# Schematic_v24.net
KiCad netlist of a schematic drawn in EAGLE
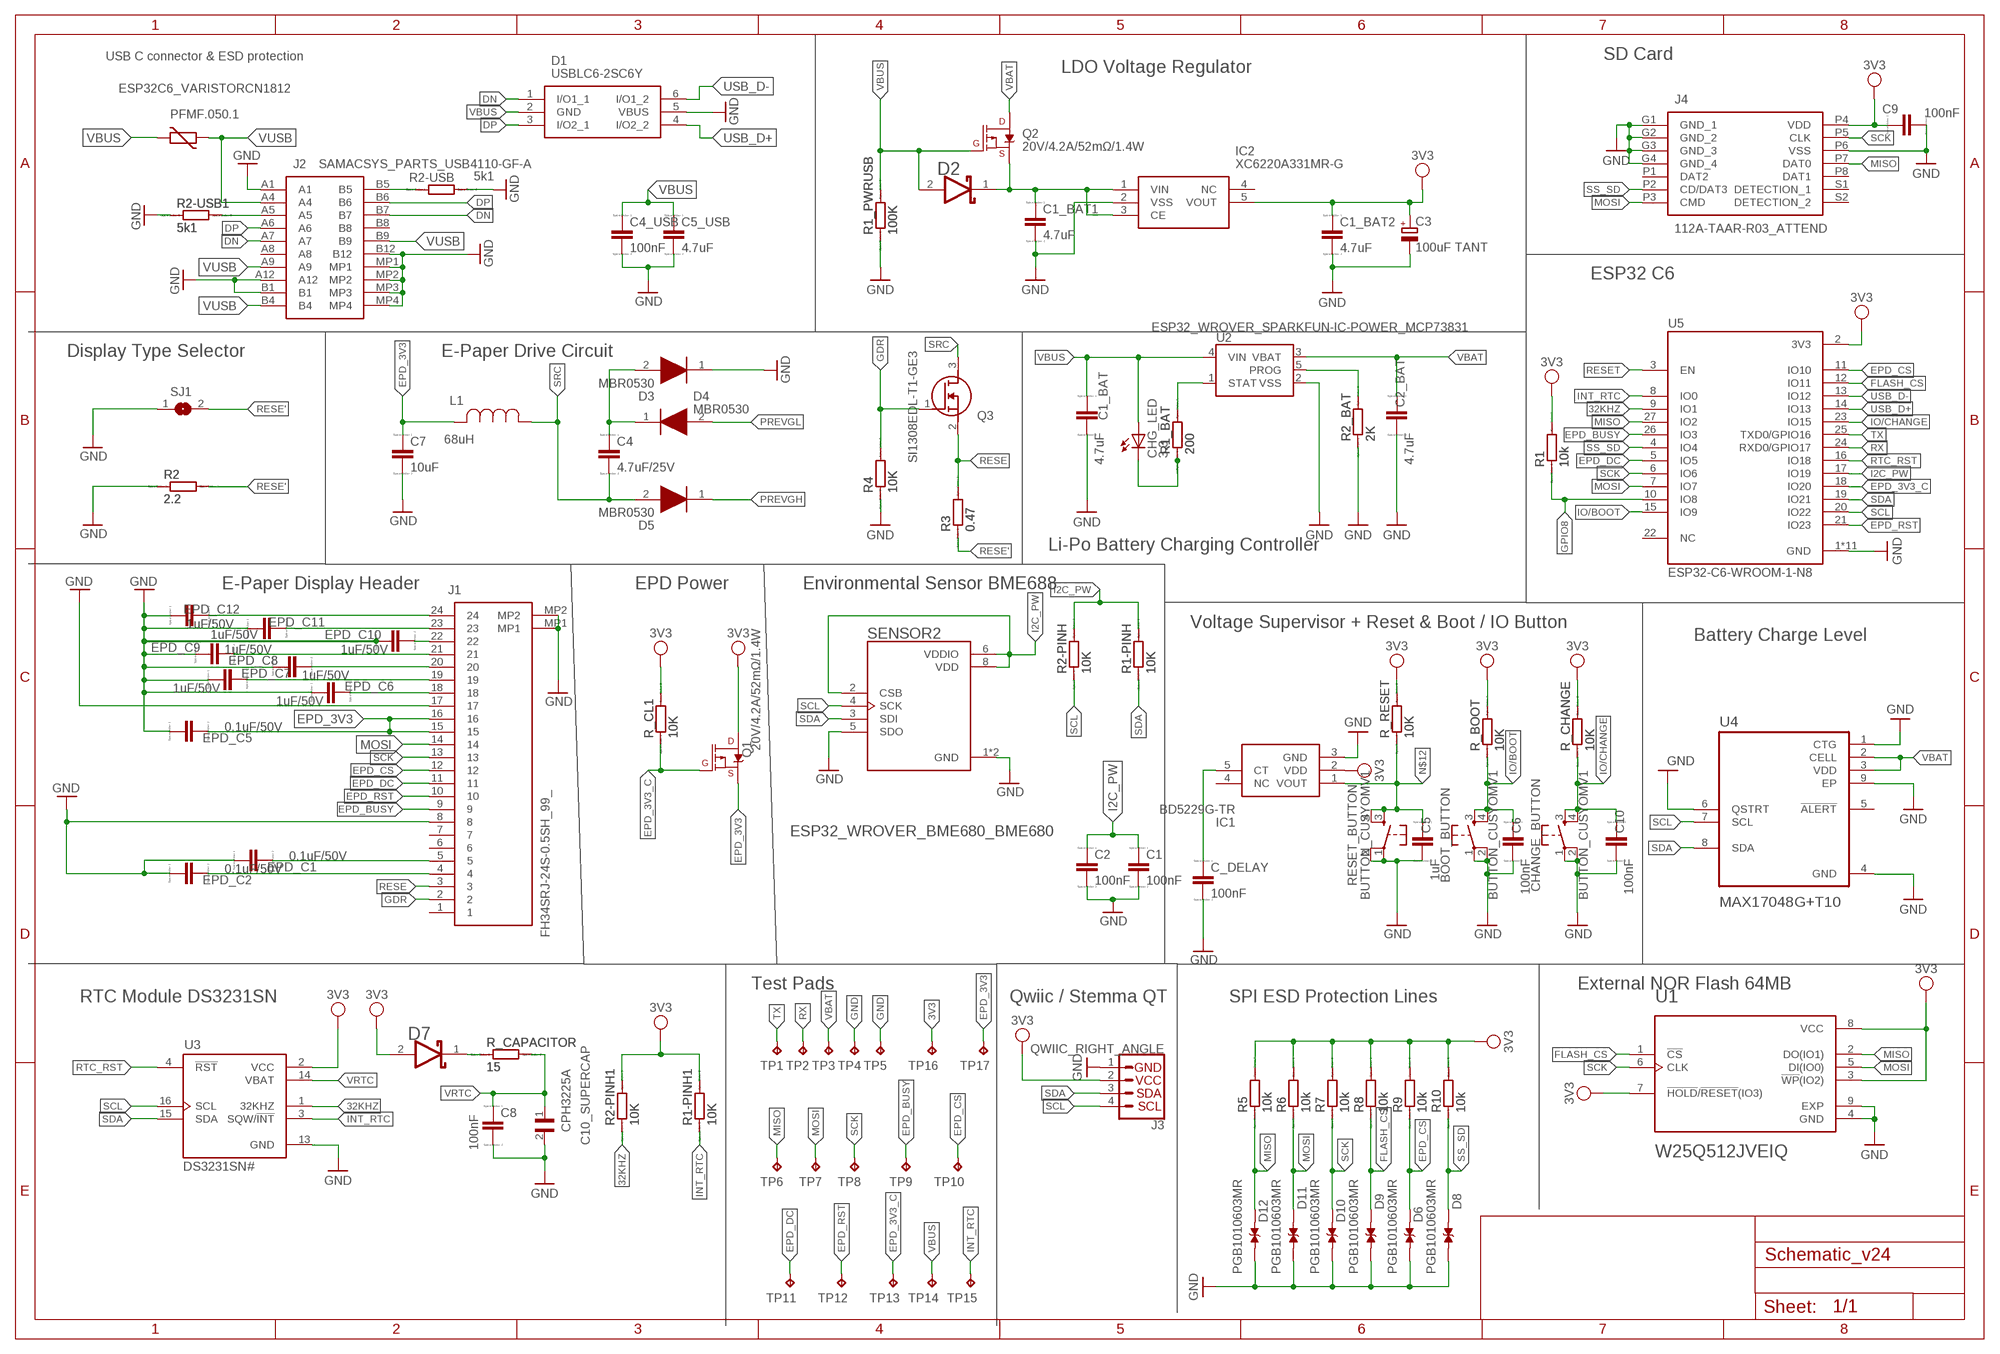
[diagram p0: schematic, sheet 1]

(export (version "E")
  (design (tool "Eeschema 10.0.6"))
  (components
    (comp (ref "BOOT_BUTTON")
      (value "BUTTON_CUSYOMV1")
      (footprint "eagle-import:MYBUTTON")
      (libsource (lib "eagle-import") (part "BUTTON_CUSYOMV1"))
    )
    (comp (ref "C1")
      (value "100nF")
      (footprint "eagle-import:ESP32_WROVER_EAGLE-LTSPICE_C0402")
      (libsource (lib "eagle-import") (part "ESP32_WROVER_EAGLE-LTSPICE_CC0402"))
    )
    (comp (ref "C1_BAT")
      (value "4.7uF")
      (footprint "eagle-import:ESP32_WROVER_EAGLE-LTSPICE_C0402")
      (libsource (lib "eagle-import") (part "ESP32_WROVER_EAGLE-LTSPICE_CC0402"))
    )
    (comp (ref "C1_BAT1")
      (value "4.7uF")
      (footprint "eagle-import:EAGLE-LTSPICE_C0402")
      (libsource (lib "eagle-import") (part "EAGLE-LTSPICE_CC0402"))
    )
    (comp (ref "C1_BAT2")
      (value "4.7uF")
      (footprint "eagle-import:EAGLE-LTSPICE_C0402")
      (libsource (lib "eagle-import") (part "EAGLE-LTSPICE_CC0402"))
    )
    (comp (ref "C2")
      (value "100nF")
      (footprint "eagle-import:ESP32_WROVER_EAGLE-LTSPICE_C0402")
      (libsource (lib "eagle-import") (part "ESP32_WROVER_EAGLE-LTSPICE_CC0402"))
    )
    (comp (ref "C2_BAT")
      (value "4.7uF")
      (footprint "eagle-import:ESP32_WROVER_EAGLE-LTSPICE_C0402")
      (libsource (lib "eagle-import") (part "ESP32_WROVER_EAGLE-LTSPICE_CC0402"))
    )
    (comp (ref "C3")
      (value "100uF TANT")
      (footprint "eagle-import:RCL_CT3528")
      (libsource (lib "eagle-import") (part "RCL_CPOL-EUCT3528"))
    )
    (comp (ref "C4")
      (value "4.7uF/25V")
      (footprint "eagle-import:ESP32_WROVER_EAGLE-LTSPICE_C0402")
      (libsource (lib "eagle-import") (part "ESP32_WROVER_EAGLE-LTSPICE_CC0402"))
    )
    (comp (ref "C4_USB")
      (value "100nF")
      (footprint "eagle-import:ESP32_WROVER_EAGLE-LTSPICE_C0402")
      (libsource (lib "eagle-import") (part "ESP32_WROVER_EAGLE-LTSPICE_CC0402"))
    )
    (comp (ref "C5")
      (value "1uF")
      (footprint "eagle-import:ESP32_WROVER_EAGLE-LTSPICE_C0402")
      (libsource (lib "eagle-import") (part "ESP32_WROVER_EAGLE-LTSPICE_CC0402"))
    )
    (comp (ref "C5_USB")
      (value "4.7uF")
      (footprint "eagle-import:ESP32_WROVER_EAGLE-LTSPICE_C0402")
      (libsource (lib "eagle-import") (part "ESP32_WROVER_EAGLE-LTSPICE_CC0402"))
    )
    (comp (ref "C6")
      (value "100nF")
      (footprint "eagle-import:ESP32_WROVER_EAGLE-LTSPICE_C0402")
      (libsource (lib "eagle-import") (part "ESP32_WROVER_EAGLE-LTSPICE_CC0402"))
    )
    (comp (ref "C7")
      (value "10uF")
      (footprint "eagle-import:ESP32_WROVER_EAGLE-LTSPICE_C0402")
      (libsource (lib "eagle-import") (part "ESP32_WROVER_EAGLE-LTSPICE_CC0402"))
    )
    (comp (ref "C8")
      (value "100nF")
      (footprint "eagle-import:ESP32_WROVER_EAGLE-LTSPICE_C0402")
      (libsource (lib "eagle-import") (part "ESP32_WROVER_EAGLE-LTSPICE_CC0402"))
    )
    (comp (ref "C9")
      (value "100nF")
      (footprint "eagle-import:ESP32_WROVER_EAGLE-LTSPICE_C0402")
      (libsource (lib "eagle-import") (part "ESP32_WROVER_EAGLE-LTSPICE_CC0402"))
    )
    (comp (ref "C10")
      (value "100nF")
      (footprint "eagle-import:ESP32_WROVER_EAGLE-LTSPICE_C0402")
      (libsource (lib "eagle-import") (part "ESP32_WROVER_EAGLE-LTSPICE_CC0402"))
    )
    (comp (ref "C10_SUPERCAP")
      (value "CPH3225A")
      (footprint "eagle-import:CAPCP3225X100N")
      (fields (field (name "MF") "Seiko Instruments"))
      (libsource (lib "eagle-import") (part "CPH3225A"))
    )
    (comp (ref "CHANGE_BUTTON")
      (value "BUTTON_CUSYOMV1")
      (footprint "eagle-import:MYBUTTON")
      (libsource (lib "eagle-import") (part "BUTTON_CUSYOMV1"))
    )
    (comp (ref "CHG_LED")
      (value "3.3")
      (footprint "eagle-import:ADAFRUIT_CHIP-LED0603")
      (libsource (lib "eagle-import") (part "ADAFRUIT_LEDCHIP-LED0603"))
    )
    (comp (ref "C_DELAY")
      (value "100nF")
      (footprint "eagle-import:ESP32_WROVER_EAGLE-LTSPICE_C0402")
      (libsource (lib "eagle-import") (part "ESP32_WROVER_EAGLE-LTSPICE_CC0402"))
    )
    (comp (ref "D1")
      (value "USBLC6-2SC6Y")
      (footprint "eagle-import:SOT95P280X145-6N")
      (fields (field (name "MF") "STMicroelectronics"))
      (libsource (lib "eagle-import") (part "USBLC6-2SC6Y"))
    )
    (comp (ref "D2")
      (value "ESP32_WROVER_AVX---SD0805S020S1R0_AVX_SD0805S020S1R0_0_0AVX_SD0805S020S1R0_0_0")
      (footprint "eagle-import:ESP32_WROVER_AVX---SD0805S020S1R0_AVX_SD0805S020S1R0_0")
      (fields
        (field (name "DIGIKEY_PART_NUMBER") "478-7800-1-ND")
        (field (name "MF") "AVX")
        (field (name "MOUSER_PART_NUMBER") "581-SD0805S020S1R0")
      )
      (libsource (lib "eagle-import") (part "ESP32_WROVER_AVX---SD0805S020S1R0_AVX_SD0805S020S1R0_0_0AVX_SD0805S020S1R0_0_0"))
    )
    (comp (ref "D3")
      (value "MBR0530")
      (footprint "eagle-import:SOD3716X135N")
      (fields (field (name "MF") "ON Semiconductor"))
      (libsource (lib "eagle-import") (part "MBR0530"))
    )
    (comp (ref "D4")
      (value "MBR0530")
      (footprint "eagle-import:SOD3716X135N")
      (fields (field (name "MF") "ON Semiconductor"))
      (libsource (lib "eagle-import") (part "MBR0530"))
    )
    (comp (ref "D5")
      (value "MBR0530")
      (footprint "eagle-import:SOD3716X135N")
      (fields (field (name "MF") "ON Semiconductor"))
      (libsource (lib "eagle-import") (part "MBR0530"))
    )
    (comp (ref "D6")
      (value "PGB1010603MR")
      (footprint "eagle-import:DIOC1608X36N")
      (fields (field (name "MF") "Littelfuse Inc."))
      (libsource (lib "eagle-import") (part "PGB1010603MR"))
    )
    (comp (ref "D7")
      (value "ESP32_WROVER_AVX---SD0805S020S1R0_AVX_SD0805S020S1R0_0_0AVX_SD0805S020S1R0_0_0")
      (footprint "eagle-import:ESP32_WROVER_AVX---SD0805S020S1R0_AVX_SD0805S020S1R0_0")
      (fields
        (field (name "DIGIKEY_PART_NUMBER") "478-7800-1-ND")
        (field (name "MF") "AVX")
        (field (name "MOUSER_PART_NUMBER") "581-SD0805S020S1R0")
      )
      (libsource (lib "eagle-import") (part "ESP32_WROVER_AVX---SD0805S020S1R0_AVX_SD0805S020S1R0_0_0AVX_SD0805S020S1R0_0_0"))
    )
    (comp (ref "D8")
      (value "PGB1010603MR")
      (footprint "eagle-import:DIOC1608X36N")
      (fields (field (name "MF") "Littelfuse Inc."))
      (libsource (lib "eagle-import") (part "PGB1010603MR"))
    )
    (comp (ref "D9")
      (value "PGB1010603MR")
      (footprint "eagle-import:DIOC1608X36N")
      (fields (field (name "MF") "Littelfuse Inc."))
      (libsource (lib "eagle-import") (part "PGB1010603MR"))
    )
    (comp (ref "D10")
      (value "PGB1010603MR")
      (footprint "eagle-import:DIOC1608X36N")
      (fields (field (name "MF") "Littelfuse Inc."))
      (libsource (lib "eagle-import") (part "PGB1010603MR"))
    )
    (comp (ref "D11")
      (value "PGB1010603MR")
      (footprint "eagle-import:DIOC1608X36N")
      (fields (field (name "MF") "Littelfuse Inc."))
      (libsource (lib "eagle-import") (part "PGB1010603MR"))
    )
    (comp (ref "D12")
      (value "PGB1010603MR")
      (footprint "eagle-import:DIOC1608X36N")
      (fields (field (name "MF") "Littelfuse Inc."))
      (libsource (lib "eagle-import") (part "PGB1010603MR"))
    )
    (comp (ref "EPD_C1")
      (value "0.1uF/50V")
      (footprint "eagle-import:ESP32_WROVER_EAGLE-LTSPICE_C0402")
      (libsource (lib "eagle-import") (part "ESP32_WROVER_EAGLE-LTSPICE_CC0402"))
    )
    (comp (ref "EPD_C2")
      (value "0.1uF/50V")
      (footprint "eagle-import:ESP32_WROVER_EAGLE-LTSPICE_C0402")
      (libsource (lib "eagle-import") (part "ESP32_WROVER_EAGLE-LTSPICE_CC0402"))
    )
    (comp (ref "EPD_C5")
      (value "0.1uF/50V")
      (footprint "eagle-import:ESP32_WROVER_EAGLE-LTSPICE_C0402")
      (libsource (lib "eagle-import") (part "ESP32_WROVER_EAGLE-LTSPICE_CC0402"))
    )
    (comp (ref "EPD_C6")
      (value "1uF/50V")
      (footprint "eagle-import:ESP32_WROVER_EAGLE-LTSPICE_C0402")
      (libsource (lib "eagle-import") (part "ESP32_WROVER_EAGLE-LTSPICE_CC0402"))
    )
    (comp (ref "EPD_C7")
      (value "1uF/50V")
      (footprint "eagle-import:ESP32_WROVER_EAGLE-LTSPICE_C0402")
      (libsource (lib "eagle-import") (part "ESP32_WROVER_EAGLE-LTSPICE_CC0402"))
    )
    (comp (ref "EPD_C8")
      (value "1uF/50V")
      (footprint "eagle-import:ESP32_WROVER_EAGLE-LTSPICE_C0402")
      (libsource (lib "eagle-import") (part "ESP32_WROVER_EAGLE-LTSPICE_CC0402"))
    )
    (comp (ref "EPD_C9")
      (value "1uF/50V")
      (footprint "eagle-import:ESP32_WROVER_EAGLE-LTSPICE_C0402")
      (libsource (lib "eagle-import") (part "ESP32_WROVER_EAGLE-LTSPICE_CC0402"))
    )
    (comp (ref "EPD_C10")
      (value "1uF/50V")
      (footprint "eagle-import:ESP32_WROVER_EAGLE-LTSPICE_C0402")
      (libsource (lib "eagle-import") (part "ESP32_WROVER_EAGLE-LTSPICE_CC0402"))
    )
    (comp (ref "EPD_C11")
      (value "1uF/50V")
      (footprint "eagle-import:ESP32_WROVER_EAGLE-LTSPICE_C0402")
      (libsource (lib "eagle-import") (part "ESP32_WROVER_EAGLE-LTSPICE_CC0402"))
    )
    (comp (ref "EPD_C12")
      (value "1uF/50V")
      (footprint "eagle-import:ESP32_WROVER_EAGLE-LTSPICE_C0402")
      (libsource (lib "eagle-import") (part "ESP32_WROVER_EAGLE-LTSPICE_CC0402"))
    )
    (comp (ref "IC1")
      (value "BD5229G-TR")
      (footprint "eagle-import:SOT95P280X125-5N")
      (fields (field (name "MOUSER_PART_NUMBER") "755-BD5229G-TR"))
      (libsource (lib "eagle-import") (part "BD5229G-TR"))
    )
    (comp (ref "IC2")
      (value "XC6220A331MR-G")
      (footprint "eagle-import:SOT95P280X120-5N")
      (fields (field (name "MOUSER_PART_NUMBER") "865-XC6220A331MR-G"))
      (libsource (lib "eagle-import") (part "XC6220A331MR-G"))
    )
    (comp (ref "J1")
      (value "FH34SRJ-24S-0.5SH_99_")
      (footprint "eagle-import:FH34SRJ24S05SH99")
      (fields
        (field (name "MANUFACTURER_PART_NUMBER") "FH34SRJ-24S-0.5SH(99)")
        (field (name "MOUSER_PART_NUMBER") "798-FH34SRJ24S05SH99")
      )
      (libsource (lib "eagle-import") (part "FH34SRJ-24S-0.5SH_99_"))
    )
    (comp (ref "J2")
      (value "SAMACSYS_PARTS_USB4110-GF-A")
      (footprint "eagle-import:SAMACSYS_PARTS_USB4110GFA")
      (fields
        (field (name "MANUFACTURER_PART_NUMBER") "USB4110-GF-A")
        (field (name "MOUSER_PART_NUMBER") "640-USB4110-GF-A")
      )
      (libsource (lib "eagle-import") (part "SAMACSYS_PARTS_USB4110-GF-A"))
    )
    (comp (ref "J3")
      (value "QWIIC_RIGHT_ANGLE")
      (footprint "eagle-import:JST04_1MM_RA")
      (libsource (lib "eagle-import") (part "QWIIC_CONNECTORJS-1MM"))
    )
    (comp (ref "J4")
      (value "112A-TAAR-R03_ATTEND")
      (footprint "eagle-import:112ATAARR03ATTEND")
      (fields (field (name "MANUFACTURER_PART_NUMBER") "112A-TAAR-R03 ATTEND"))
      (libsource (lib "eagle-import") (part "112A-TAAR-R03_ATTEND"))
    )
    (comp (ref "L1")
      (value "68uH")
      (footprint "eagle-import:IND_4828-WE-TPC_WRE")
      (fields
        (field (name "MANUFACTURER_PART_NUMBER") "744043680")
        (field (name "COPYRIGHT") "Copyright (C) 2024 Ultra Librarian. All rights reserved.")
      )
      (libsource (lib "eagle-import") (part "744043680IND_4828-WE-TPC_WRE"))
    )
    (comp (ref "PFMF.050.1")
      (value "ESP32C6_VARISTORCN1812")
      (footprint "eagle-import:ESP32C6_VARISTOR_CT_CN1812")
      (libsource (lib "eagle-import") (part "ESP32C6_VARISTORCN1812"))
    )
    (comp (ref "Q1")
      (value "20V/4.2A/52mΩ/1.4W")
      (footprint "eagle-import:ESP32_WROVER_SPARKFUN-DISCRETESEMI_SOT23-3")
      (libsource (lib "eagle-import") (part "ESP32_WROVER_SPARKFUN-DISCRETESEMI_MOSFET_PCH-DMG2305UX-7"))
    )
    (comp (ref "Q2")
      (value "20V/4.2A/52mΩ/1.4W")
      (footprint "eagle-import:ESP32_WROVER_SPARKFUN-DISCRETESEMI_SOT23-3")
      (libsource (lib "eagle-import") (part "ESP32_WROVER_SPARKFUN-DISCRETESEMI_MOSFET_PCH-DMG2305UX-7"))
    )
    (comp (ref "Q3")
      (value "SI1308EDL-T1-GE3")
      (footprint "eagle-import:SOT65P210X110-3N")
      (fields (field (name "MF") "Vishay Siliconix"))
      (libsource (lib "eagle-import") (part "SI1308EDL-T1-GE3"))
    )
    (comp (ref "R1")
      (value "10k")
      (footprint "eagle-import:ESP32_WROVER_EAGLE-LTSPICE_R0402")
      (libsource (lib "eagle-import") (part "ESP32_WROVER_EAGLE-LTSPICE_RR0402"))
    )
    (comp (ref "R1-PINH")
      (value "10K")
      (footprint "eagle-import:ESP32_WROVER_EAGLE-LTSPICE_R0402")
      (libsource (lib "eagle-import") (part "ESP32_WROVER_EAGLE-LTSPICE_RR0402"))
    )
    (comp (ref "R1-PINH1")
      (value "10K")
      (footprint "eagle-import:ESP32_WROVER_EAGLE-LTSPICE_R0402")
      (libsource (lib "eagle-import") (part "ESP32_WROVER_EAGLE-LTSPICE_RR0402"))
    )
    (comp (ref "R1_BAT")
      (value "200")
      (footprint "eagle-import:ESP32_WROVER_EAGLE-LTSPICE_R0402")
      (libsource (lib "eagle-import") (part "ESP32_WROVER_EAGLE-LTSPICE_RR0402"))
    )
    (comp (ref "R1_PWRUSB")
      (value "100K")
      (footprint "eagle-import:ESP32_WROVER_EAGLE-LTSPICE_R0402")
      (libsource (lib "eagle-import") (part "ESP32_WROVER_EAGLE-LTSPICE_RR0402"))
    )
    (comp (ref "R2")
      (value "2.2")
      (footprint "eagle-import:ESP32_WROVER_EAGLE-LTSPICE_R0402")
      (libsource (lib "eagle-import") (part "ESP32_WROVER_EAGLE-LTSPICE_RR0402"))
    )
    (comp (ref "R2-PINH")
      (value "10K")
      (footprint "eagle-import:ESP32_WROVER_EAGLE-LTSPICE_R0402")
      (libsource (lib "eagle-import") (part "ESP32_WROVER_EAGLE-LTSPICE_RR0402"))
    )
    (comp (ref "R2-PINH1")
      (value "10K")
      (footprint "eagle-import:ESP32_WROVER_EAGLE-LTSPICE_R0402")
      (libsource (lib "eagle-import") (part "ESP32_WROVER_EAGLE-LTSPICE_RR0402"))
    )
    (comp (ref "R2-USB")
      (value "5k1")
      (footprint "eagle-import:ESP32_WROVER_EAGLE-LTSPICE_R0402")
      (libsource (lib "eagle-import") (part "ESP32_WROVER_EAGLE-LTSPICE_RR0402"))
    )
    (comp (ref "R2-USB1")
      (value "5k1")
      (footprint "eagle-import:ESP32_WROVER_EAGLE-LTSPICE_R0402")
      (libsource (lib "eagle-import") (part "ESP32_WROVER_EAGLE-LTSPICE_RR0402"))
    )
    (comp (ref "R2_BAT")
      (value "2K")
      (footprint "eagle-import:ESP32_WROVER_EAGLE-LTSPICE_R0402")
      (libsource (lib "eagle-import") (part "ESP32_WROVER_EAGLE-LTSPICE_RR0402"))
    )
    (comp (ref "R3")
      (value "0.47")
      (footprint "eagle-import:ESP32_WROVER_EAGLE-LTSPICE_R0402")
      (libsource (lib "eagle-import") (part "ESP32_WROVER_EAGLE-LTSPICE_RR0402"))
    )
    (comp (ref "R4")
      (value "10K")
      (footprint "eagle-import:ESP32_WROVER_EAGLE-LTSPICE_R0402")
      (libsource (lib "eagle-import") (part "ESP32_WROVER_EAGLE-LTSPICE_RR0402"))
    )
    (comp (ref "R5")
      (value "10k")
      (footprint "eagle-import:ESP32_WROVER_EAGLE-LTSPICE_R0402")
      (libsource (lib "eagle-import") (part "ESP32_WROVER_EAGLE-LTSPICE_RR0402"))
    )
    (comp (ref "R6")
      (value "10k")
      (footprint "eagle-import:ESP32_WROVER_EAGLE-LTSPICE_R0402")
      (libsource (lib "eagle-import") (part "ESP32_WROVER_EAGLE-LTSPICE_RR0402"))
    )
    (comp (ref "R7")
      (value "10k")
      (footprint "eagle-import:ESP32_WROVER_EAGLE-LTSPICE_R0402")
      (libsource (lib "eagle-import") (part "ESP32_WROVER_EAGLE-LTSPICE_RR0402"))
    )
    (comp (ref "R8")
      (value "10k")
      (footprint "eagle-import:ESP32_WROVER_EAGLE-LTSPICE_R0402")
      (libsource (lib "eagle-import") (part "ESP32_WROVER_EAGLE-LTSPICE_RR0402"))
    )
    (comp (ref "R9")
      (value "10k")
      (footprint "eagle-import:ESP32_WROVER_EAGLE-LTSPICE_R0402")
      (libsource (lib "eagle-import") (part "ESP32_WROVER_EAGLE-LTSPICE_RR0402"))
    )
    (comp (ref "R10")
      (value "10k")
      (footprint "eagle-import:ESP32_WROVER_EAGLE-LTSPICE_R0402")
      (libsource (lib "eagle-import") (part "ESP32_WROVER_EAGLE-LTSPICE_RR0402"))
    )
    (comp (ref "RESET_BUTTON")
      (value "BUTTON_CUSYOMV1")
      (footprint "eagle-import:MYBUTTON")
      (libsource (lib "eagle-import") (part "BUTTON_CUSYOMV1"))
    )
    (comp (ref "R_BOOT")
      (value "10K")
      (footprint "eagle-import:ESP32_WROVER_EAGLE-LTSPICE_R0402")
      (libsource (lib "eagle-import") (part "ESP32_WROVER_EAGLE-LTSPICE_RR0402"))
    )
    (comp (ref "R_CAPACITOR")
      (value "15")
      (footprint "eagle-import:ESP32_WROVER_EAGLE-LTSPICE_R0402")
      (libsource (lib "eagle-import") (part "ESP32_WROVER_EAGLE-LTSPICE_RR0402"))
    )
    (comp (ref "R_CHANGE")
      (value "10K")
      (footprint "eagle-import:ESP32_WROVER_EAGLE-LTSPICE_R0402")
      (libsource (lib "eagle-import") (part "ESP32_WROVER_EAGLE-LTSPICE_RR0402"))
    )
    (comp (ref "R_CL1")
      (value "10K")
      (footprint "eagle-import:ESP32_WROVER_EAGLE-LTSPICE_R0402")
      (libsource (lib "eagle-import") (part "ESP32_WROVER_EAGLE-LTSPICE_RR0402"))
    )
    (comp (ref "R_RESET")
      (value "10K")
      (footprint "eagle-import:ESP32_WROVER_EAGLE-LTSPICE_R0402")
      (libsource (lib "eagle-import") (part "ESP32_WROVER_EAGLE-LTSPICE_RR0402"))
    )
    (comp (ref "SENSOR2")
      (value "ESP32_WROVER_BME680_BME680")
      (footprint "eagle-import:ESP32_WROVER_BME680_PSON80P300X300X100-8N")
      (fields (field (name "MF") "Bosch Sensortec") (field (name "MP") "BME680"))
      (libsource (lib "eagle-import") (part "ESP32_WROVER_BME680_BME680"))
    )
    (comp (ref "SJ1") (value "SJ") (footprint "eagle-import:SJ") (libsource (lib "eagle-import") (part "SJ")))
    (comp (ref "TP1")
      (value "TPTP20R")
      (footprint "eagle-import:TP20R")
      (libsource (lib "eagle-import") (part "TPTP20R"))
    )
    (comp (ref "TP2")
      (value "TPTP20R")
      (footprint "eagle-import:TP20R")
      (libsource (lib "eagle-import") (part "TPTP20R"))
    )
    (comp (ref "TP3")
      (value "TPTP20R")
      (footprint "eagle-import:TP20R")
      (libsource (lib "eagle-import") (part "TPTP20R"))
    )
    (comp (ref "TP4")
      (value "TPTP20R")
      (footprint "eagle-import:TP20R")
      (libsource (lib "eagle-import") (part "TPTP20R"))
    )
    (comp (ref "TP5")
      (value "TPTP20R")
      (footprint "eagle-import:TP20R")
      (libsource (lib "eagle-import") (part "TPTP20R"))
    )
    (comp (ref "TP6")
      (value "TPTP20R")
      (footprint "eagle-import:TP20R")
      (libsource (lib "eagle-import") (part "TPTP20R"))
    )
    (comp (ref "TP7")
      (value "TPTP20R")
      (footprint "eagle-import:TP20R")
      (libsource (lib "eagle-import") (part "TPTP20R"))
    )
    (comp (ref "TP8")
      (value "TPTP20R")
      (footprint "eagle-import:TP20R")
      (libsource (lib "eagle-import") (part "TPTP20R"))
    )
    (comp (ref "TP9")
      (value "TPTP20R")
      (footprint "eagle-import:TP20R")
      (libsource (lib "eagle-import") (part "TPTP20R"))
    )
    (comp (ref "TP10")
      (value "TPTP20R")
      (footprint "eagle-import:TP20R")
      (libsource (lib "eagle-import") (part "TPTP20R"))
    )
    (comp (ref "TP11")
      (value "TPTP20R")
      (footprint "eagle-import:TP20R")
      (libsource (lib "eagle-import") (part "TPTP20R"))
    )
    (comp (ref "TP12")
      (value "TPTP20R")
      (footprint "eagle-import:TP20R")
      (libsource (lib "eagle-import") (part "TPTP20R"))
    )
    (comp (ref "TP13")
      (value "TPTP20R")
      (footprint "eagle-import:TP20R")
      (libsource (lib "eagle-import") (part "TPTP20R"))
    )
    (comp (ref "TP14")
      (value "TPTP20R")
      (footprint "eagle-import:TP20R")
      (libsource (lib "eagle-import") (part "TPTP20R"))
    )
    (comp (ref "TP15")
      (value "TPTP20R")
      (footprint "eagle-import:TP20R")
      (libsource (lib "eagle-import") (part "TPTP20R"))
    )
    (comp (ref "TP16")
      (value "TPTP20R")
      (footprint "eagle-import:TP20R")
      (libsource (lib "eagle-import") (part "TPTP20R"))
    )
    (comp (ref "TP17")
      (value "TPTP20R")
      (footprint "eagle-import:TP20R")
      (libsource (lib "eagle-import") (part "TPTP20R"))
    )
    (comp (ref "U1")
      (value "W25Q512JVEIQ")
      (footprint "eagle-import:SON127P600X800X80-9N")
      (fields (field (name "MF") "Winbond Electronics"))
      (libsource (lib "eagle-import") (part "W25Q512JVEIQ"))
    )
    (comp (ref "U2")
      (value "ESP32_WROVER_SPARKFUN-IC-POWER_MCP73831")
      (footprint "eagle-import:ESP32_WROVER_SPARKFUN-IC-POWER_SOT23-5")
      (libsource (lib "eagle-import") (part "ESP32_WROVER_SPARKFUN-IC-POWER_MCP73831"))
    )
    (comp (ref "U3")
      (value "DS3231SN#")
      (footprint "eagle-import:SOIC127P1032X265-16N")
      (fields (field (name "MF") "Analog Devices"))
      (libsource (lib "eagle-import") (part "DS3231SN#"))
    )
    (comp (ref "U4")
      (value "MAX17048G+T10")
      (footprint "eagle-import:SON50P200X200X80-9N")
      (fields (field (name "MF") "Analog Devices"))
      (libsource (lib "eagle-import") (part "MAX17048G+T10"))
    )
    (comp (ref "U5")
      (value "ESP32-C6-WROOM-1-N8")
      (footprint "eagle-import:XCVR_ESP32-C6-WROOM-1-N8")
      (fields (field (name "MF") "Espressif Systems"))
      (libsource (lib "eagle-import") (part "ESP32-C6-WROOM-1-N8"))
    )
  )
  (nets
    (net (code "1") (name "3V3") (class "Default")
      (node (ref "C1_BAT2") (pin "1") (pinfunction "1_1") (pintype "passive"))
      (node (ref "C3") (pin "+") (pinfunction "+_+") (pintype "passive"))
      (node (ref "C9") (pin "1") (pinfunction "1_1") (pintype "passive"))
      (node (ref "D7") (pin "2") (pinfunction "ANODE_2") (pintype "bidirectional"))
      (node (ref "IC1") (pin "2") (pinfunction "VDD_2") (pintype "bidirectional"))
      (node (ref "IC2") (pin "5") (pinfunction "VOUT_5") (pintype "bidirectional"))
      (node (ref "J3") (pin "2") (pinfunction "2_2") (pintype "power_in"))
      (node (ref "J4") (pin "P4") (pinfunction "VDD_P4") (pintype "bidirectional"))
      (node (ref "Q1") (pin "3") (pinfunction "D_3") (pintype "bidirectional"))
      (node (ref "R1") (pin "2") (pinfunction "2_2") (pintype "passive"))
      (node (ref "R1-PINH1") (pin "2") (pinfunction "2_2") (pintype "passive"))
      (node (ref "R10") (pin "2") (pinfunction "2_2") (pintype "passive"))
      (node (ref "R2-PINH1") (pin "2") (pinfunction "2_2") (pintype "passive"))
      (node (ref "R5") (pin "2") (pinfunction "2_2") (pintype "passive"))
      (node (ref "R6") (pin "2") (pinfunction "2_2") (pintype "passive"))
      (node (ref "R7") (pin "2") (pinfunction "2_2") (pintype "passive"))
      (node (ref "R8") (pin "2") (pinfunction "2_2") (pintype "passive"))
      (node (ref "R9") (pin "2") (pinfunction "2_2") (pintype "passive"))
      (node (ref "R_BOOT") (pin "2") (pinfunction "2_2") (pintype "passive"))
      (node (ref "R_CHANGE") (pin "2") (pinfunction "2_2") (pintype "passive"))
      (node (ref "R_CL1") (pin "2") (pinfunction "2_2") (pintype "passive"))
      (node (ref "R_RESET") (pin "2") (pinfunction "2_2") (pintype "passive"))
      (node (ref "TP16") (pin "TP") (pinfunction "TP_TP") (pintype "input"))
      (node (ref "U1") (pin "3") (pinfunction "~{WP}(IO2)_3") (pintype "bidirectional"))
      (node (ref "U1") (pin "7") (pinfunction "~{HOLD}/~{RESET}(IO3)_7") (pintype "bidirectional"))
      (node (ref "U1") (pin "8") (pinfunction "VCC_8") (pintype "power_in"))
      (node (ref "U3") (pin "2") (pinfunction "VCC_2") (pintype "power_in"))
      (node (ref "U5") (pin "2") (pinfunction "3V3_2") (pintype "power_in"))
    )
    (net (code "2") (name "32KHZ") (class "Default")
      (node (ref "R2-PINH1") (pin "1") (pinfunction "1_1") (pintype "passive"))
      (node (ref "U3") (pin "1") (pinfunction "32KHZ_1") (pintype "output"))
      (node (ref "U5") (pin "9") (pinfunction "IO1_9") (pintype "bidirectional"))
    )
    (net (code "3") (name "DN") (class "Default")
      (node (ref "D1") (pin "1") (pinfunction "I/O1_1_1") (pintype "bidirectional"))
      (node (ref "J2") (pin "A7") (pinfunction "A7_A7") (pintype "bidirectional"))
      (node (ref "J2") (pin "B7") (pinfunction "B7_B7") (pintype "bidirectional"))
    )
    (net (code "4") (name "DP") (class "Default")
      (node (ref "D1") (pin "3") (pinfunction "I/O2_1_3") (pintype "bidirectional"))
      (node (ref "J2") (pin "A6") (pinfunction "A6_A6") (pintype "bidirectional"))
      (node (ref "J2") (pin "B6") (pinfunction "B6_B6") (pintype "bidirectional"))
    )
    (net (code "5") (name "EPD_3V3") (class "Default")
      (node (ref "C7") (pin "1") (pinfunction "1_1") (pintype "passive"))
      (node (ref "EPD_C5") (pin "2") (pinfunction "2_2") (pintype "passive"))
      (node (ref "J1") (pin "15") (pinfunction "15_15") (pintype "bidirectional"))
      (node (ref "J1") (pin "16") (pinfunction "16_16") (pintype "bidirectional"))
      (node (ref "L1") (pin "2") (pinfunction "2_2") (pintype "passive"))
      (node (ref "Q1") (pin "2") (pinfunction "S_2") (pintype "bidirectional"))
      (node (ref "TP17") (pin "TP") (pinfunction "TP_TP") (pintype "input"))
    )
    (net (code "6") (name "EPD_3V3_C") (class "Default")
      (node (ref "Q1") (pin "1") (pinfunction "G_1") (pintype "bidirectional"))
      (node (ref "R_CL1") (pin "1") (pinfunction "1_1") (pintype "passive"))
      (node (ref "TP13") (pin "TP") (pinfunction "TP_TP") (pintype "input"))
      (node (ref "U5") (pin "18") (pinfunction "IO20_18") (pintype "bidirectional"))
    )
    (net (code "7") (name "EPD_BUSY") (class "Default")
      (node (ref "J1") (pin "9") (pinfunction "9_9") (pintype "bidirectional"))
      (node (ref "TP9") (pin "TP") (pinfunction "TP_TP") (pintype "input"))
      (node (ref "U5") (pin "26") (pinfunction "IO3_26") (pintype "bidirectional"))
    )
    (net (code "8") (name "EPD_CS") (class "Default")
      (node (ref "D6") (pin "2") (pinfunction "2_2") (pintype "passive"))
      (node (ref "J1") (pin "12") (pinfunction "12_12") (pintype "bidirectional"))
      (node (ref "R9") (pin "1") (pinfunction "1_1") (pintype "passive"))
      (node (ref "TP10") (pin "TP") (pinfunction "TP_TP") (pintype "input"))
      (node (ref "U5") (pin "11") (pinfunction "IO10_11") (pintype "bidirectional"))
    )
    (net (code "9") (name "EPD_DC") (class "Default")
      (node (ref "J1") (pin "11") (pinfunction "11_11") (pintype "bidirectional"))
      (node (ref "TP11") (pin "TP") (pinfunction "TP_TP") (pintype "input"))
      (node (ref "U5") (pin "5") (pinfunction "IO5_5") (pintype "bidirectional"))
    )
    (net (code "10") (name "EPD_RST") (class "Default")
      (node (ref "J1") (pin "10") (pinfunction "10_10") (pintype "bidirectional"))
      (node (ref "TP12") (pin "TP") (pinfunction "TP_TP") (pintype "input"))
      (node (ref "U5") (pin "21") (pinfunction "IO23_21") (pintype "bidirectional"))
    )
    (net (code "11") (name "FLASH_CS") (class "Default")
      (node (ref "D9") (pin "2") (pinfunction "2_2") (pintype "passive"))
      (node (ref "R8") (pin "1") (pinfunction "1_1") (pintype "passive"))
      (node (ref "U1") (pin "1") (pinfunction "~{CS}_1") (pintype "input"))
      (node (ref "U5") (pin "12") (pinfunction "IO11_12") (pintype "bidirectional"))
    )
    (net (code "12") (name "GDR") (class "Default")
      (node (ref "J1") (pin "2") (pinfunction "2_2") (pintype "bidirectional"))
      (node (ref "Q3") (pin "1") (pinfunction "G_1") (pintype "bidirectional"))
      (node (ref "R4") (pin "2") (pinfunction "2_2") (pintype "passive"))
    )
    (net (code "13") (name "GND") (class "Default")
      (node (ref "BOOT_BUTTON") (pin "1") (pinfunction "1_1") (pintype "passive"))
      (node (ref "BOOT_BUTTON") (pin "2") (pinfunction "2_2") (pintype "passive"))
      (node (ref "C1") (pin "2") (pinfunction "2_2") (pintype "passive"))
      (node (ref "C10") (pin "2") (pinfunction "2_2") (pintype "passive"))
      (node (ref "C10_SUPERCAP") (pin "2") (pinfunction "2_2") (pintype "passive"))
      (node (ref "C1_BAT") (pin "2") (pinfunction "2_2") (pintype "passive"))
      (node (ref "C1_BAT1") (pin "2") (pinfunction "2_2") (pintype "passive"))
      (node (ref "C1_BAT2") (pin "2") (pinfunction "2_2") (pintype "passive"))
      (node (ref "C2") (pin "2") (pinfunction "2_2") (pintype "passive"))
      (node (ref "C2_BAT") (pin "2") (pinfunction "2_2") (pintype "passive"))
      (node (ref "C3") (pin "-") (pinfunction "-_-") (pintype "passive"))
      (node (ref "C4_USB") (pin "2") (pinfunction "2_2") (pintype "passive"))
      (node (ref "C5") (pin "2") (pinfunction "2_2") (pintype "passive"))
      (node (ref "C5_USB") (pin "2") (pinfunction "2_2") (pintype "passive"))
      (node (ref "C6") (pin "2") (pinfunction "2_2") (pintype "passive"))
      (node (ref "C7") (pin "2") (pinfunction "2_2") (pintype "passive"))
      (node (ref "C8") (pin "2") (pinfunction "2_2") (pintype "passive"))
      (node (ref "C9") (pin "2") (pinfunction "2_2") (pintype "passive"))
      (node (ref "CHANGE_BUTTON") (pin "1") (pinfunction "1_1") (pintype "passive"))
      (node (ref "CHANGE_BUTTON") (pin "2") (pinfunction "2_2") (pintype "passive"))
      (node (ref "C_DELAY") (pin "2") (pinfunction "2_2") (pintype "passive"))
      (node (ref "D1") (pin "5") (pinfunction "VBUS_5") (pintype "bidirectional"))
      (node (ref "D10") (pin "1") (pinfunction "1_1") (pintype "passive"))
      (node (ref "D11") (pin "1") (pinfunction "1_1") (pintype "passive"))
      (node (ref "D12") (pin "1") (pinfunction "1_1") (pintype "passive"))
      (node (ref "D3") (pin "1") (pinfunction "K_1") (pintype "bidirectional"))
      (node (ref "D6") (pin "1") (pinfunction "1_1") (pintype "passive"))
      (node (ref "D8") (pin "1") (pinfunction "1_1") (pintype "passive"))
      (node (ref "D9") (pin "1") (pinfunction "1_1") (pintype "passive"))
      (node (ref "EPD_C1") (pin "1") (pinfunction "1_1") (pintype "passive"))
      (node (ref "EPD_C10") (pin "1") (pinfunction "1_1") (pintype "passive"))
      (node (ref "EPD_C11") (pin "1") (pinfunction "1_1") (pintype "passive"))
      (node (ref "EPD_C12") (pin "1") (pinfunction "1_1") (pintype "passive"))
      (node (ref "EPD_C2") (pin "1") (pinfunction "1_1") (pintype "passive"))
      (node (ref "EPD_C5") (pin "1") (pinfunction "1_1") (pintype "passive"))
      (node (ref "EPD_C6") (pin "1") (pinfunction "1_1") (pintype "passive"))
      (node (ref "EPD_C7") (pin "1") (pinfunction "1_1") (pintype "passive"))
      (node (ref "EPD_C8") (pin "1") (pinfunction "1_1") (pintype "passive"))
      (node (ref "EPD_C9") (pin "1") (pinfunction "1_1") (pintype "passive"))
      (node (ref "IC1") (pin "3") (pinfunction "GND_3") (pintype "bidirectional"))
      (node (ref "IC2") (pin "2") (pinfunction "VSS_2") (pintype "bidirectional"))
      (node (ref "J1") (pin "17") (pinfunction "17_17") (pintype "bidirectional"))
      (node (ref "J1") (pin "8") (pinfunction "8_8") (pintype "bidirectional"))
      (node (ref "J1") (pin "MP1") (pinfunction "MP1_MP1") (pintype "bidirectional"))
      (node (ref "J1") (pin "MP2") (pinfunction "MP2_MP2") (pintype "bidirectional"))
      (node (ref "J2") (pin "A1") (pinfunction "A1_A1") (pintype "bidirectional"))
      (node (ref "J2") (pin "A12") (pinfunction "A12_A12") (pintype "bidirectional"))
      (node (ref "J2") (pin "B1") (pinfunction "B1_B1") (pintype "bidirectional"))
      (node (ref "J2") (pin "B12") (pinfunction "B12_B12") (pintype "bidirectional"))
      (node (ref "J2") (pin "MP1") (pinfunction "MP1_MP1") (pintype "bidirectional"))
      (node (ref "J2") (pin "MP2") (pinfunction "MP2_MP2") (pintype "bidirectional"))
      (node (ref "J2") (pin "MP3") (pinfunction "MP3_MP3") (pintype "bidirectional"))
      (node (ref "J2") (pin "MP4") (pinfunction "MP4_MP4") (pintype "bidirectional"))
      (node (ref "J3") (pin "1") (pinfunction "1_1") (pintype "power_in"))
      (node (ref "J4") (pin "G1") (pinfunction "GND_1_G1") (pintype "bidirectional"))
      (node (ref "J4") (pin "G2") (pinfunction "GND_2_G2") (pintype "bidirectional"))
      (node (ref "J4") (pin "G3") (pinfunction "GND_3_G3") (pintype "bidirectional"))
      (node (ref "J4") (pin "G4") (pinfunction "GND_4_G4") (pintype "bidirectional"))
      (node (ref "J4") (pin "P6") (pinfunction "VSS_P6") (pintype "bidirectional"))
      (node (ref "R1_PWRUSB") (pin "1") (pinfunction "1_1") (pintype "passive"))
      (node (ref "R2") (pin "1") (pinfunction "1_1") (pintype "passive"))
      (node (ref "R2-USB") (pin "2") (pinfunction "2_2") (pintype "passive"))
      (node (ref "R2-USB1") (pin "1") (pinfunction "1_1") (pintype "passive"))
      (node (ref "R2_BAT") (pin "1") (pinfunction "1_1") (pintype "passive"))
      (node (ref "R4") (pin "1") (pinfunction "1_1") (pintype "passive"))
      (node (ref "RESET_BUTTON") (pin "1") (pinfunction "1_1") (pintype "passive"))
      (node (ref "RESET_BUTTON") (pin "2") (pinfunction "2_2") (pintype "passive"))
      (node (ref "SENSOR2") (pin "1") (pinfunction "GND_1") (pintype "power_in"))
      (node (ref "SENSOR2") (pin "5") (pinfunction "SDO_5") (pintype "bidirectional"))
      (node (ref "SENSOR2") (pin "7") (pinfunction "GND_7") (pintype "power_in"))
      (node (ref "SJ1") (pin "1") (pinfunction "1_1") (pintype "passive"))
      (node (ref "TP4") (pin "TP") (pinfunction "TP_TP") (pintype "input"))
      (node (ref "TP5") (pin "TP") (pinfunction "TP_TP") (pintype "input"))
      (node (ref "U1") (pin "4") (pinfunction "GND_4") (pintype "power_in"))
      (node (ref "U1") (pin "9") (pinfunction "EXP_9") (pintype "passive"))
      (node (ref "U2") (pin "2") (pinfunction "VSS_2") (pintype "power_in"))
      (node (ref "U3") (pin "13") (pinfunction "GND_13") (pintype "power_in"))
      (node (ref "U4") (pin "1") (pinfunction "CTG_1") (pintype "power_in"))
      (node (ref "U4") (pin "4") (pinfunction "GND_4") (pintype "power_in"))
      (node (ref "U4") (pin "6") (pinfunction "QSTRT_6") (pintype "input"))
      (node (ref "U4") (pin "9") (pinfunction "EP_9") (pintype "power_in"))
      (node (ref "U5") (pin "1") (pinfunction "GND_1") (pintype "power_in"))
      (node (ref "U5") (pin "28") (pinfunction "GND_28") (pintype "power_in"))
      (node (ref "U5") (pin "29_1") (pinfunction "GND_29_1") (pintype "power_in"))
      (node (ref "U5") (pin "29_2") (pinfunction "GND_29_2") (pintype "power_in"))
      (node (ref "U5") (pin "29_3") (pinfunction "GND_29_3") (pintype "power_in"))
      (node (ref "U5") (pin "29_4") (pinfunction "GND_29_4") (pintype "power_in"))
      (node (ref "U5") (pin "29_5") (pinfunction "GND_29_5") (pintype "power_in"))
      (node (ref "U5") (pin "29_6") (pinfunction "GND_29_6") (pintype "power_in"))
      (node (ref "U5") (pin "29_7") (pinfunction "GND_29_7") (pintype "power_in"))
      (node (ref "U5") (pin "29_8") (pinfunction "GND_29_8") (pintype "power_in"))
      (node (ref "U5") (pin "29_9") (pinfunction "GND_29_9") (pintype "power_in"))
    )
    (net (code "14") (name "GPIO8") (class "Default")
      (node (ref "R1") (pin "1") (pinfunction "1_1") (pintype "passive"))
      (node (ref "U5") (pin "10") (pinfunction "IO8_10") (pintype "bidirectional"))
    )
    (net (code "15") (name "I2C_PW") (class "Default")
      (node (ref "C1") (pin "1") (pinfunction "1_1") (pintype "passive"))
      (node (ref "C2") (pin "1") (pinfunction "1_1") (pintype "passive"))
      (node (ref "R1-PINH") (pin "2") (pinfunction "2_2") (pintype "passive"))
      (node (ref "R2-PINH") (pin "2") (pinfunction "2_2") (pintype "passive"))
      (node (ref "SENSOR2") (pin "2") (pinfunction "CSB_2") (pintype "input"))
      (node (ref "SENSOR2") (pin "6") (pinfunction "VDDIO_6") (pintype "power_in"))
      (node (ref "SENSOR2") (pin "8") (pinfunction "VDD_8") (pintype "power_in"))
      (node (ref "U5") (pin "17") (pinfunction "IO19_17") (pintype "bidirectional"))
    )
    (net (code "16") (name "INT_RTC") (class "Default")
      (node (ref "R1-PINH1") (pin "1") (pinfunction "1_1") (pintype "passive"))
      (node (ref "TP15") (pin "TP") (pinfunction "TP_TP") (pintype "input"))
      (node (ref "U3") (pin "3") (pinfunction "SQW/~{INT}_3") (pintype "output"))
      (node (ref "U5") (pin "8") (pinfunction "IO0_8") (pintype "bidirectional"))
    )
    (net (code "17") (name "IO{slash}BOOT") (class "Default")
      (node (ref "BOOT_BUTTON") (pin "3") (pinfunction "3_3") (pintype "passive"))
      (node (ref "BOOT_BUTTON") (pin "4") (pinfunction "4_4") (pintype "passive"))
      (node (ref "C6") (pin "1") (pinfunction "1_1") (pintype "passive"))
      (node (ref "R_BOOT") (pin "1") (pinfunction "1_1") (pintype "passive"))
      (node (ref "U5") (pin "15") (pinfunction "IO9_15") (pintype "bidirectional"))
    )
    (net (code "18") (name "IO{slash}CHANGE") (class "Default")
      (node (ref "C10") (pin "1") (pinfunction "1_1") (pintype "passive"))
      (node (ref "CHANGE_BUTTON") (pin "3") (pinfunction "3_3") (pintype "passive"))
      (node (ref "CHANGE_BUTTON") (pin "4") (pinfunction "4_4") (pintype "passive"))
      (node (ref "R_CHANGE") (pin "1") (pinfunction "1_1") (pintype "passive"))
      (node (ref "U5") (pin "23") (pinfunction "IO15_23") (pintype "bidirectional"))
    )
    (net (code "19") (name "MISO") (class "Default")
      (node (ref "D12") (pin "2") (pinfunction "2_2") (pintype "passive"))
      (node (ref "J4") (pin "P7") (pinfunction "DAT0_P7") (pintype "bidirectional"))
      (node (ref "R5") (pin "1") (pinfunction "1_1") (pintype "passive"))
      (node (ref "TP6") (pin "TP") (pinfunction "TP_TP") (pintype "input"))
      (node (ref "U1") (pin "2") (pinfunction "DO(IO1)_2") (pintype "bidirectional"))
      (node (ref "U5") (pin "27") (pinfunction "IO2_27") (pintype "bidirectional"))
    )
    (net (code "20") (name "MOSI") (class "Default")
      (node (ref "D11") (pin "2") (pinfunction "2_2") (pintype "passive"))
      (node (ref "J1") (pin "14") (pinfunction "14_14") (pintype "bidirectional"))
      (node (ref "J4") (pin "P3") (pinfunction "CMD_P3") (pintype "bidirectional"))
      (node (ref "R6") (pin "1") (pinfunction "1_1") (pintype "passive"))
      (node (ref "TP7") (pin "TP") (pinfunction "TP_TP") (pintype "input"))
      (node (ref "U1") (pin "5") (pinfunction "DI(IO0)_5") (pintype "bidirectional"))
      (node (ref "U5") (pin "7") (pinfunction "IO7_7") (pintype "bidirectional"))
    )
    (net (code "21") (name "N$12") (class "Default")
      (node (ref "C5") (pin "1") (pinfunction "1_1") (pintype "passive"))
      (node (ref "IC1") (pin "1") (pinfunction "VOUT_1") (pintype "bidirectional"))
      (node (ref "RESET_BUTTON") (pin "3") (pinfunction "3_3") (pintype "passive"))
      (node (ref "RESET_BUTTON") (pin "4") (pinfunction "4_4") (pintype "passive"))
      (node (ref "R_RESET") (pin "1") (pinfunction "1_1") (pintype "passive"))
    )
    (net (code "22") (name "Net-(CHG_LED-PadC)") (class "Default")
      (node (ref "CHG_LED") (pin "C") (pinfunction "C_C") (pintype "passive"))
      (node (ref "R1_BAT") (pin "1") (pinfunction "1_1") (pintype "passive"))
    )
    (net (code "23") (name "Net-(D2-CATHODE)") (class "Default")
      (node (ref "C1_BAT1") (pin "1") (pinfunction "1_1") (pintype "passive"))
      (node (ref "D2") (pin "1") (pinfunction "CATHODE_1") (pintype "bidirectional"))
      (node (ref "IC2") (pin "1") (pinfunction "VIN_1") (pintype "bidirectional"))
      (node (ref "IC2") (pin "3") (pinfunction "CE_3") (pintype "bidirectional"))
      (node (ref "Q2") (pin "2") (pinfunction "S_2") (pintype "bidirectional"))
    )
    (net (code "24") (name "Net-(D3-A)") (class "Default")
      (node (ref "C4") (pin "1") (pinfunction "1_1") (pintype "passive"))
      (node (ref "D3") (pin "2") (pinfunction "A_2") (pintype "bidirectional"))
      (node (ref "D4") (pin "1") (pinfunction "K_1") (pintype "bidirectional"))
    )
    (net (code "25") (name "Net-(D7-CATHODE)") (class "Default")
      (node (ref "D7") (pin "1") (pinfunction "CATHODE_1") (pintype "bidirectional"))
      (node (ref "R_CAPACITOR") (pin "1") (pinfunction "1_1") (pintype "passive"))
    )
    (net (code "26") (name "Net-(EPD_C1-Pad2)") (class "Default")
      (node (ref "EPD_C1") (pin "2") (pinfunction "2_2") (pintype "passive"))
      (node (ref "J1") (pin "5") (pinfunction "5_5") (pintype "bidirectional"))
    )
    (net (code "27") (name "Net-(EPD_C2-Pad2)") (class "Default")
      (node (ref "EPD_C2") (pin "2") (pinfunction "2_2") (pintype "passive"))
      (node (ref "J1") (pin "4") (pinfunction "4_4") (pintype "bidirectional"))
    )
    (net (code "28") (name "Net-(EPD_C6-Pad2)") (class "Default")
      (node (ref "EPD_C6") (pin "2") (pinfunction "2_2") (pintype "passive"))
      (node (ref "J1") (pin "18") (pinfunction "18_18") (pintype "bidirectional"))
    )
    (net (code "29") (name "Net-(EPD_C7-Pad2)") (class "Default")
      (node (ref "EPD_C7") (pin "2") (pinfunction "2_2") (pintype "passive"))
      (node (ref "J1") (pin "19") (pinfunction "19_19") (pintype "bidirectional"))
    )
    (net (code "30") (name "Net-(EPD_C8-Pad2)") (class "Default")
      (node (ref "EPD_C8") (pin "2") (pinfunction "2_2") (pintype "passive"))
      (node (ref "J1") (pin "20") (pinfunction "20_20") (pintype "bidirectional"))
    )
    (net (code "31") (name "Net-(EPD_C9-Pad2)") (class "Default")
      (node (ref "EPD_C9") (pin "2") (pinfunction "2_2") (pintype "passive"))
      (node (ref "J1") (pin "21") (pinfunction "21_21") (pintype "bidirectional"))
    )
    (net (code "32") (name "Net-(EPD_C10-Pad2)") (class "Default")
      (node (ref "EPD_C10") (pin "2") (pinfunction "2_2") (pintype "passive"))
      (node (ref "J1") (pin "22") (pinfunction "22_22") (pintype "bidirectional"))
    )
    (net (code "33") (name "Net-(EPD_C11-Pad2)") (class "Default")
      (node (ref "EPD_C11") (pin "2") (pinfunction "2_2") (pintype "passive"))
      (node (ref "J1") (pin "23") (pinfunction "23_23") (pintype "bidirectional"))
    )
    (net (code "34") (name "Net-(EPD_C12-Pad2)") (class "Default")
      (node (ref "EPD_C12") (pin "2") (pinfunction "2_2") (pintype "passive"))
      (node (ref "J1") (pin "24") (pinfunction "24_24") (pintype "bidirectional"))
    )
    (net (code "35") (name "Net-(IC1-CT)") (class "Default")
      (node (ref "C_DELAY") (pin "1") (pinfunction "1_1") (pintype "passive"))
      (node (ref "IC1") (pin "5") (pinfunction "CT_5") (pintype "bidirectional"))
    )
    (net (code "36") (name "Net-(J2-PadA5)") (class "Default")
      (node (ref "J2") (pin "A5") (pinfunction "A5_A5") (pintype "bidirectional"))
      (node (ref "R2-USB1") (pin "2") (pinfunction "2_2") (pintype "passive"))
    )
    (net (code "37") (name "Net-(J2-PadB5)") (class "Default")
      (node (ref "J2") (pin "B5") (pinfunction "B5_B5") (pintype "bidirectional"))
      (node (ref "R2-USB") (pin "1") (pinfunction "1_1") (pintype "passive"))
    )
    (net (code "38") (name "Net-(U2-PROG)") (class "Default")
      (node (ref "R2_BAT") (pin "2") (pinfunction "2_2") (pintype "passive"))
      (node (ref "U2") (pin "5") (pinfunction "PROG_5") (pintype "input"))
    )
    (net (code "39") (name "Net-(U2-STAT)") (class "Default")
      (node (ref "R1_BAT") (pin "2") (pinfunction "2_2") (pintype "passive"))
      (node (ref "U2") (pin "1") (pinfunction "STAT_1") (pintype "output"))
    )
    (net (code "40") (name "PREVGH") (class "Default")
      (node (ref "D5") (pin "1") (pinfunction "K_1") (pintype "bidirectional"))
    )
    (net (code "41") (name "PREVGL") (class "Default")
      (node (ref "D4") (pin "2") (pinfunction "A_2") (pintype "bidirectional"))
    )
    (net (code "42") (name "RESE") (class "Default")
      (node (ref "J1") (pin "3") (pinfunction "3_3") (pintype "bidirectional"))
      (node (ref "Q3") (pin "2") (pinfunction "S_2") (pintype "bidirectional"))
      (node (ref "R3") (pin "2") (pinfunction "2_2") (pintype "passive"))
    )
    (net (code "43") (name "RESE'") (class "Default")
      (node (ref "R2") (pin "2") (pinfunction "2_2") (pintype "passive"))
      (node (ref "R3") (pin "1") (pinfunction "1_1") (pintype "passive"))
      (node (ref "SJ1") (pin "2") (pinfunction "2_2") (pintype "passive"))
    )
    (net (code "44") (name "RESET") (class "Default")
      (node (ref "U5") (pin "3") (pinfunction "EN_3") (pintype "input"))
    )
    (net (code "45") (name "RTC_RST") (class "Default")
      (node (ref "U3") (pin "4") (pinfunction "~{RST}_4") (pintype "input"))
      (node (ref "U5") (pin "16") (pinfunction "IO18_16") (pintype "bidirectional"))
    )
    (net (code "46") (name "RX") (class "Default")
      (node (ref "TP2") (pin "TP") (pinfunction "TP_TP") (pintype "input"))
      (node (ref "U5") (pin "24") (pinfunction "RXD0/GPIO17_24") (pintype "bidirectional"))
    )
    (net (code "47") (name "SCK") (class "Default")
      (node (ref "D10") (pin "2") (pinfunction "2_2") (pintype "passive"))
      (node (ref "J1") (pin "13") (pinfunction "13_13") (pintype "bidirectional"))
      (node (ref "J4") (pin "P5") (pinfunction "CLK_P5") (pintype "bidirectional"))
      (node (ref "R7") (pin "1") (pinfunction "1_1") (pintype "passive"))
      (node (ref "TP8") (pin "TP") (pinfunction "TP_TP") (pintype "input"))
      (node (ref "U1") (pin "6") (pinfunction "CLK_6") (pintype "input"))
      (node (ref "U5") (pin "6") (pinfunction "IO6_6") (pintype "bidirectional"))
    )
    (net (code "48") (name "SCL") (class "Default")
      (node (ref "J3") (pin "4") (pinfunction "4_4") (pintype "passive"))
      (node (ref "R2-PINH") (pin "1") (pinfunction "1_1") (pintype "passive"))
      (node (ref "SENSOR2") (pin "4") (pinfunction "SCK_4") (pintype "input"))
      (node (ref "U3") (pin "16") (pinfunction "SCL_16") (pintype "input"))
      (node (ref "U4") (pin "7") (pinfunction "SCL_7") (pintype "input"))
      (node (ref "U5") (pin "20") (pinfunction "IO22_20") (pintype "bidirectional"))
    )
    (net (code "49") (name "SDA") (class "Default")
      (node (ref "J3") (pin "3") (pinfunction "3_3") (pintype "passive"))
      (node (ref "R1-PINH") (pin "1") (pinfunction "1_1") (pintype "passive"))
      (node (ref "SENSOR2") (pin "3") (pinfunction "SDI_3") (pintype "bidirectional"))
      (node (ref "U3") (pin "15") (pinfunction "SDA_15") (pintype "bidirectional"))
      (node (ref "U4") (pin "8") (pinfunction "SDA_8") (pintype "bidirectional"))
      (node (ref "U5") (pin "19") (pinfunction "IO21_19") (pintype "bidirectional"))
    )
    (net (code "50") (name "SRC") (class "Default")
      (node (ref "C4") (pin "2") (pinfunction "2_2") (pintype "passive"))
      (node (ref "D5") (pin "2") (pinfunction "A_2") (pintype "bidirectional"))
      (node (ref "L1") (pin "1") (pinfunction "1_1") (pintype "passive"))
      (node (ref "Q3") (pin "3") (pinfunction "D_3") (pintype "bidirectional"))
    )
    (net (code "51") (name "SS_SD") (class "Default")
      (node (ref "D8") (pin "2") (pinfunction "2_2") (pintype "passive"))
      (node (ref "J4") (pin "P2") (pinfunction "CD/DAT3_P2") (pintype "bidirectional"))
      (node (ref "R10") (pin "1") (pinfunction "1_1") (pintype "passive"))
      (node (ref "U5") (pin "4") (pinfunction "IO4_4") (pintype "bidirectional"))
    )
    (net (code "52") (name "TX") (class "Default")
      (node (ref "TP1") (pin "TP") (pinfunction "TP_TP") (pintype "input"))
      (node (ref "U5") (pin "25") (pinfunction "TXD0/GPIO16_25") (pintype "bidirectional"))
    )
    (net (code "53") (name "USB_D+") (class "Default")
      (node (ref "D1") (pin "4") (pinfunction "I/O2_2_4") (pintype "bidirectional"))
      (node (ref "U5") (pin "14") (pinfunction "IO13_14") (pintype "bidirectional"))
    )
    (net (code "54") (name "USB_D-") (class "Default")
      (node (ref "D1") (pin "6") (pinfunction "I/O1_2_6") (pintype "bidirectional"))
      (node (ref "U5") (pin "13") (pinfunction "IO12_13") (pintype "bidirectional"))
    )
    (net (code "55") (name "VBAT") (class "Default")
      (node (ref "C2_BAT") (pin "1") (pinfunction "1_1") (pintype "passive"))
      (node (ref "Q2") (pin "3") (pinfunction "D_3") (pintype "bidirectional"))
      (node (ref "TP3") (pin "TP") (pinfunction "TP_TP") (pintype "input"))
      (node (ref "U2") (pin "3") (pinfunction "VBAT_3") (pintype "power_in"))
      (node (ref "U4") (pin "2") (pinfunction "CELL_2") (pintype "power_in"))
      (node (ref "U4") (pin "3") (pinfunction "VDD_3") (pintype "power_in"))
    )
    (net (code "56") (name "VBUS") (class "Default")
      (node (ref "C1_BAT") (pin "1") (pinfunction "1_1") (pintype "passive"))
      (node (ref "C4_USB") (pin "1") (pinfunction "1_1") (pintype "passive"))
      (node (ref "C5_USB") (pin "1") (pinfunction "1_1") (pintype "passive"))
      (node (ref "CHG_LED") (pin "A") (pinfunction "A_A") (pintype "passive"))
      (node (ref "D1") (pin "2") (pinfunction "GND_2") (pintype "bidirectional"))
      (node (ref "D2") (pin "2") (pinfunction "ANODE_2") (pintype "bidirectional"))
      (node (ref "PFMF.050.1") (pin "2") (pinfunction "2_2") (pintype "passive"))
      (node (ref "Q2") (pin "1") (pinfunction "G_1") (pintype "bidirectional"))
      (node (ref "R1_PWRUSB") (pin "2") (pinfunction "2_2") (pintype "passive"))
      (node (ref "TP14") (pin "TP") (pinfunction "TP_TP") (pintype "input"))
      (node (ref "U2") (pin "4") (pinfunction "VIN_4") (pintype "power_in"))
    )
    (net (code "57") (name "VRTC") (class "Default")
      (node (ref "C10_SUPERCAP") (pin "1") (pinfunction "1_1") (pintype "passive"))
      (node (ref "C8") (pin "1") (pinfunction "1_1") (pintype "passive"))
      (node (ref "R_CAPACITOR") (pin "2") (pinfunction "2_2") (pintype "passive"))
      (node (ref "U3") (pin "14") (pinfunction "VBAT_14") (pintype "power_in"))
    )
    (net (code "58") (name "VUSB") (class "Default")
      (node (ref "J2") (pin "A4") (pinfunction "A4_A4") (pintype "bidirectional"))
      (node (ref "J2") (pin "A9") (pinfunction "A9_A9") (pintype "bidirectional"))
      (node (ref "J2") (pin "B4") (pinfunction "B4_B4") (pintype "bidirectional"))
      (node (ref "J2") (pin "B9") (pinfunction "B9_B9") (pintype "bidirectional"))
      (node (ref "PFMF.050.1") (pin "1") (pinfunction "1_1") (pintype "passive"))
    )
    (net (code "59") (name "unconnected-(IC1-NC-Pad4)") (class "Default")
      (node (ref "IC1") (pin "4") (pinfunction "NC_4") (pintype "no_connect"))
    )
    (net (code "60") (name "unconnected-(IC2-NC-Pad4)") (class "Default")
      (node (ref "IC2") (pin "4") (pinfunction "NC_4") (pintype "no_connect"))
    )
    (net (code "61") (name "unconnected-(J1-Pad1)") (class "Default")
      (node (ref "J1") (pin "1") (pinfunction "1_1") (pintype "bidirectional"))
    )
    (net (code "62") (name "unconnected-(J1-Pad6)") (class "Default")
      (node (ref "J1") (pin "6") (pinfunction "6_6") (pintype "bidirectional"))
    )
    (net (code "63") (name "unconnected-(J1-Pad7)") (class "Default")
      (node (ref "J1") (pin "7") (pinfunction "7_7") (pintype "bidirectional"))
    )
    (net (code "64") (name "unconnected-(J2-PadA8)") (class "Default")
      (node (ref "J2") (pin "A8") (pinfunction "A8_A8") (pintype "bidirectional"))
    )
    (net (code "65") (name "unconnected-(J2-PadB8)") (class "Default")
      (node (ref "J2") (pin "B8") (pinfunction "B8_B8") (pintype "bidirectional"))
    )
    (net (code "66") (name "unconnected-(J4-DAT1-PadP8)") (class "Default")
      (node (ref "J4") (pin "P8") (pinfunction "DAT1_P8") (pintype "bidirectional"))
    )
    (net (code "67") (name "unconnected-(J4-DAT2-PadP1)") (class "Default")
      (node (ref "J4") (pin "P1") (pinfunction "DAT2_P1") (pintype "bidirectional"))
    )
    (net (code "68") (name "unconnected-(J4-DETECTION_1-PadS1)") (class "Default")
      (node (ref "J4") (pin "S1") (pinfunction "DETECTION_1_S1") (pintype "bidirectional"))
    )
    (net (code "69") (name "unconnected-(J4-DETECTION_2-PadS2)") (class "Default")
      (node (ref "J4") (pin "S2") (pinfunction "DETECTION_2_S2") (pintype "bidirectional"))
    )
    (net (code "70") (name "unconnected-(U4-~{ALERT}-Pad5)") (class "Default")
      (node (ref "U4") (pin "5") (pinfunction "~{ALERT}_5") (pintype "output"))
    )
    (net (code "71") (name "unconnected-(U5-NC-Pad22)") (class "Default")
      (node (ref "U5") (pin "22") (pinfunction "NC_22") (pintype "no_connect"))
    )
  )
)
